# LED_Indi.net
KiCad netlist of a schematic drawn in Altium Designer
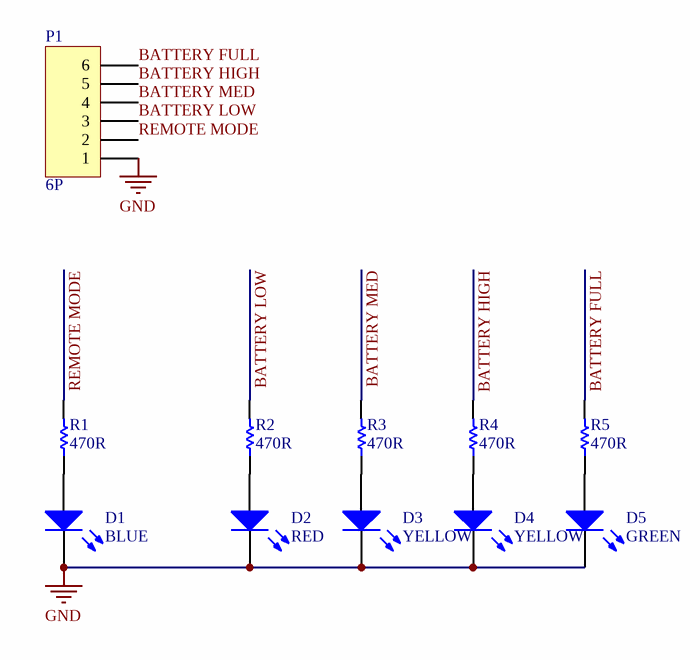
[diagram p0: LED_Indi.SchDoc]

(export (version "E")
  (design (tool "Eeschema 10.0.6"))
  (components
    (comp (ref "D1")
      (value "BLUE")
      (footprint "LED0805")
      (description "Typical INFRARED GaAs LED")
      (fields (field (name "Comment") "LED dán 0805BLUE") (field (name "PUBLISHER") "*"))
      (libsource (lib "DnsSchLib") (part "LED0"))
    )
    (comp (ref "D2")
      (value "RED")
      (footprint "LED0805")
      (description "Typical INFRARED GaAs LED")
      (fields (field (name "Comment") "LED dán 0805RED") (field (name "PUBLISHER") "*"))
      (libsource (lib "DnsSchLib") (part "LED0"))
    )
    (comp (ref "D3")
      (value "YELLOW")
      (footprint "LED0805")
      (description "Typical INFRARED GaAs LED")
      (fields (field (name "Comment") "LED dán 0805YELLOW") (field (name "PUBLISHER") "*"))
      (libsource (lib "DnsSchLib") (part "LED0"))
    )
    (comp (ref "D4")
      (value "YELLOW")
      (footprint "LED0805")
      (description "Typical INFRARED GaAs LED")
      (fields (field (name "Comment") "LED dán 0805YELLOW") (field (name "PUBLISHER") "*"))
      (libsource (lib "DnsSchLib") (part "LED0"))
    )
    (comp (ref "D5")
      (value "GREEN")
      (footprint "LED0805")
      (description "Typical INFRARED GaAs LED")
      (fields (field (name "Comment") "LED dán 0805GREEN") (field (name "PUBLISHER") "*"))
      (libsource (lib "DnsSchLib") (part "LED0"))
    )
    (comp (ref "P1")
      (value "6P")
      (footprint "HDR1X6H")
      (description "Header, 6-Pin, Right Angle")
      (fields
        (field (name "Comment") "Jump đực chân thẳng, 2.54mm 6P")
        (field (name "PUBLISHER") "Altium Limited")
      )
      (libsource (lib "Miscellaneous Connectors") (part "Header 6H"))
    )
    (comp (ref "R1")
      (value "470R")
      (footprint "0805DD")
      (description "Semiconductor Resistor")
      (fields (field (name "Comment") "Điện trở dán 0805470R") (field (name "PUBLISHER") "*"))
      (libsource (lib "DnsSchLib") (part "Res Semi"))
    )
    (comp (ref "R2")
      (value "470R")
      (footprint "0805DD")
      (description "Semiconductor Resistor")
      (fields (field (name "Comment") "Điện trở dán 0805470R") (field (name "PUBLISHER") "*"))
      (libsource (lib "DnsSchLib") (part "Res Semi"))
    )
    (comp (ref "R3")
      (value "470R")
      (footprint "0805DD")
      (description "Semiconductor Resistor")
      (fields (field (name "Comment") "Điện trở dán 0805470R") (field (name "PUBLISHER") "*"))
      (libsource (lib "DnsSchLib") (part "Res Semi"))
    )
    (comp (ref "R4")
      (value "470R")
      (footprint "0805DD")
      (description "Semiconductor Resistor")
      (fields (field (name "Comment") "Điện trở dán 0805470R") (field (name "PUBLISHER") "*"))
      (libsource (lib "DnsSchLib") (part "Res Semi"))
    )
    (comp (ref "R5")
      (value "470R")
      (footprint "0805DD")
      (description "Semiconductor Resistor")
      (fields (field (name "Comment") "Điện trở dán 0805470R") (field (name "PUBLISHER") "*"))
      (libsource (lib "DnsSchLib") (part "Res Semi"))
    )
  )
  (nets
    (net (code "1") (name "/BATTERY FULL") (class "Default")
      (node (ref "P1") (pin "6") (pinfunction "6_6") (pintype "passive"))
      (node (ref "R5") (pin "2") (pinfunction "2_2") (pintype "passive"))
    )
    (net (code "2") (name "/BATTERY HIGH") (class "Default")
      (node (ref "P1") (pin "5") (pinfunction "5_5") (pintype "passive"))
      (node (ref "R4") (pin "2") (pinfunction "2_2") (pintype "passive"))
    )
    (net (code "3") (name "/BATTERY LOW") (class "Default")
      (node (ref "P1") (pin "3") (pinfunction "3_3") (pintype "passive"))
      (node (ref "R2") (pin "2") (pinfunction "2_2") (pintype "passive"))
    )
    (net (code "4") (name "/BATTERY MED") (class "Default")
      (node (ref "P1") (pin "4") (pinfunction "4_4") (pintype "passive"))
      (node (ref "R3") (pin "2") (pinfunction "2_2") (pintype "passive"))
    )
    (net (code "5") (name "/REMOTE MODE") (class "Default")
      (node (ref "P1") (pin "2") (pinfunction "2_2") (pintype "passive"))
      (node (ref "R1") (pin "2") (pinfunction "2_2") (pintype "passive"))
    )
    (net (code "6") (name "GND") (class "Default")
      (node (ref "D1") (pin "2") (pinfunction "K_2") (pintype "passive"))
      (node (ref "D2") (pin "2") (pinfunction "K_2") (pintype "passive"))
      (node (ref "D3") (pin "2") (pinfunction "K_2") (pintype "passive"))
      (node (ref "D4") (pin "2") (pinfunction "K_2") (pintype "passive"))
      (node (ref "D5") (pin "2") (pinfunction "K_2") (pintype "passive"))
      (node (ref "P1") (pin "1") (pinfunction "1_1") (pintype "passive"))
    )
    (net (code "7") (name "Net-(D1-A)") (class "Default")
      (node (ref "D1") (pin "1") (pinfunction "A_1") (pintype "passive"))
      (node (ref "R1") (pin "1") (pinfunction "1_1") (pintype "passive"))
    )
    (net (code "8") (name "Net-(D2-A)") (class "Default")
      (node (ref "D2") (pin "1") (pinfunction "A_1") (pintype "passive"))
      (node (ref "R2") (pin "1") (pinfunction "1_1") (pintype "passive"))
    )
    (net (code "9") (name "Net-(D3-A)") (class "Default")
      (node (ref "D3") (pin "1") (pinfunction "A_1") (pintype "passive"))
      (node (ref "R3") (pin "1") (pinfunction "1_1") (pintype "passive"))
    )
    (net (code "10") (name "Net-(D4-A)") (class "Default")
      (node (ref "D4") (pin "1") (pinfunction "A_1") (pintype "passive"))
      (node (ref "R4") (pin "1") (pinfunction "1_1") (pintype "passive"))
    )
    (net (code "11") (name "Net-(D5-A)") (class "Default")
      (node (ref "D5") (pin "1") (pinfunction "A_1") (pintype "passive"))
      (node (ref "R5") (pin "1") (pinfunction "1_1") (pintype "passive"))
    )
  )
)
